# A4980.net
KiCad netlist of a schematic drawn in EAGLE
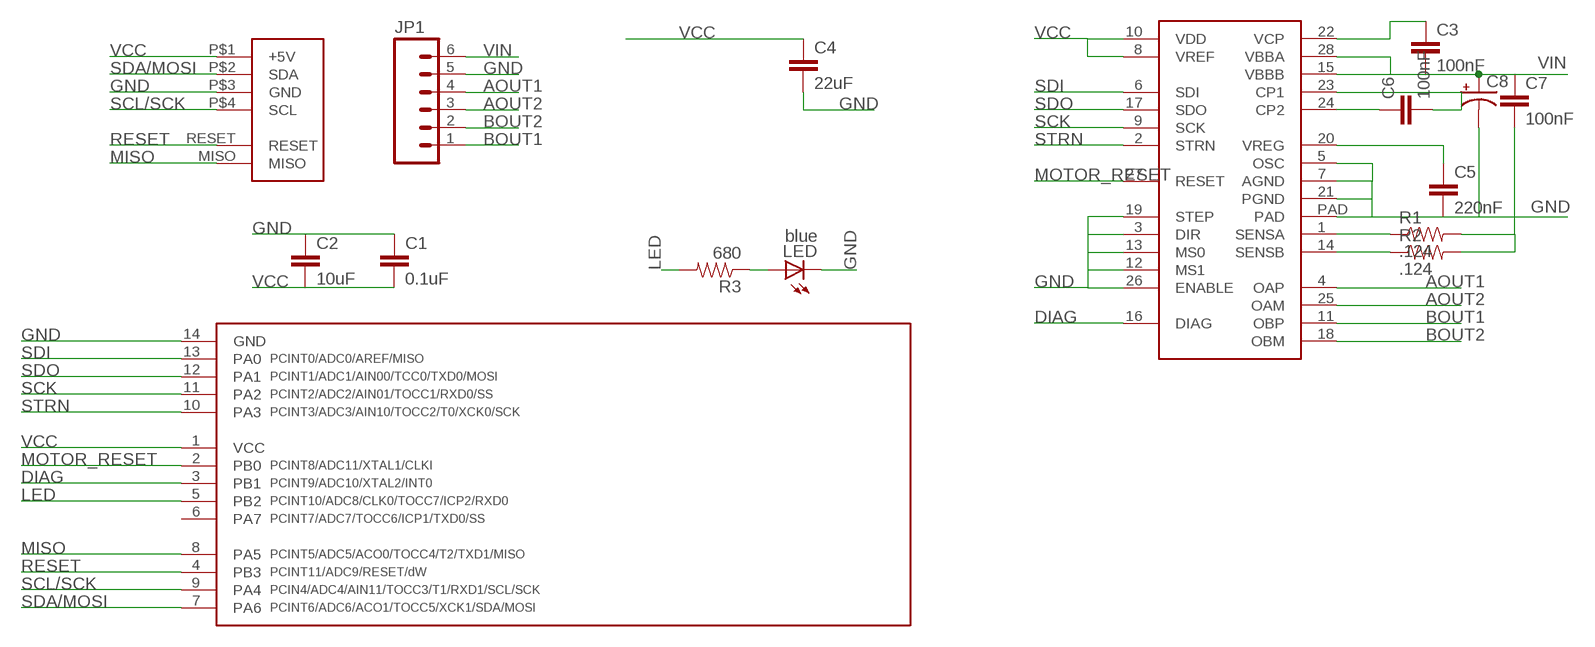
[diagram p0: schematic, sheet 1]

(export (version "E")
  (design (tool "Eeschema 10.0.6"))
  (components
    (comp (ref "C1")
      (value "0.1uF")
      (footprint "eagle-import:0805")
      (libsource (lib "eagle-import") (part "CAP0805"))
    )
    (comp (ref "C2")
      (value "10uF")
      (footprint "eagle-import:0805")
      (libsource (lib "eagle-import") (part "CAP0805"))
    )
    (comp (ref "C3")
      (value "100nF")
      (footprint "eagle-import:0805")
      (libsource (lib "eagle-import") (part "CAP0805"))
    )
    (comp (ref "C4")
      (value "22uF")
      (footprint "eagle-import:0805")
      (libsource (lib "eagle-import") (part "22UF-6.3V-20%(0805)"))
    )
    (comp (ref "C5")
      (value "220nF")
      (footprint "eagle-import:0805")
      (libsource (lib "eagle-import") (part "CAP0805"))
    )
    (comp (ref "C6")
      (value "100nF")
      (footprint "eagle-import:0805")
      (libsource (lib "eagle-import") (part "CAP0805"))
    )
    (comp (ref "C7")
      (value "100nF")
      (footprint "eagle-import:0805")
      (libsource (lib "eagle-import") (part "CAP0805"))
    )
    (comp (ref "C8")
      (value "CAP_POLD")
      (footprint "eagle-import:PANASONIC_D")
      (libsource (lib "eagle-import") (part "CAP_POLD"))
    )
    (comp (ref "JP1")
      (value "M06SIP")
      (footprint "eagle-import:1X06")
      (libsource (lib "eagle-import") (part "M06SIP"))
    )
    (comp (ref "LED")
      (value "blue")
      (footprint "eagle-import:CHIPLED_1206")
      (libsource (lib "eagle-import") (part "LEDCHIPLED_1206"))
    )
    (comp (ref "R1")
      (value ".124")
      (footprint "eagle-import:0805")
      (libsource (lib "eagle-import") (part "SparkFun-Resistors_RESISTOR0805-RES"))
    )
    (comp (ref "R2")
      (value ".124")
      (footprint "eagle-import:0805")
      (libsource (lib "eagle-import") (part "SparkFun-Resistors_RESISTOR0805-RES"))
    )
    (comp (ref "R3")
      (value "680")
      (footprint "eagle-import:0805")
      (libsource (lib "eagle-import") (part "RESISTOR0805-RES"))
    )
    (comp (ref "U$1")
      (value "A4980")
      (footprint "eagle-import:TSSOP-28")
      (libsource (lib "eagle-import") (part "A4980"))
    )
    (comp (ref "U$3")
      (value "TINY841")
      (footprint "eagle-import:SOIC14")
      (libsource (lib "eagle-import") (part "TINY841"))
    )
    (comp (ref "U$4")
      (value "FOOTPRINT")
      (footprint "eagle-import:FOOTPRINT")
      (libsource (lib "eagle-import") (part "FOOTPRINT"))
    )
  )
  (nets
    (net (code "1") (name "/AOUT1") (class "Default")
      (node (ref "JP1") (pin "4") (pinfunction "4_4") (pintype "passive"))
      (node (ref "U$1") (pin "4") (pinfunction "OAP_4") (pintype "bidirectional"))
    )
    (net (code "2") (name "/AOUT2") (class "Default")
      (node (ref "JP1") (pin "3") (pinfunction "3_3") (pintype "passive"))
      (node (ref "U$1") (pin "25") (pinfunction "OAM_25") (pintype "bidirectional"))
    )
    (net (code "3") (name "/BOUT1") (class "Default")
      (node (ref "JP1") (pin "1") (pinfunction "1_1") (pintype "passive"))
      (node (ref "U$1") (pin "11") (pinfunction "OBP_11") (pintype "bidirectional"))
    )
    (net (code "4") (name "/BOUT2") (class "Default")
      (node (ref "JP1") (pin "2") (pinfunction "2_2") (pintype "passive"))
      (node (ref "U$1") (pin "18") (pinfunction "OBM_18") (pintype "bidirectional"))
    )
    (net (code "5") (name "/DIAG") (class "Default")
      (node (ref "U$1") (pin "16") (pinfunction "DIAG_16") (pintype "bidirectional"))
      (node (ref "U$3") (pin "3") (pinfunction "PB1_3") (pintype "bidirectional"))
    )
    (net (code "6") (name "/GND") (class "Default")
      (node (ref "C1") (pin "1") (pinfunction "1_1") (pintype "passive"))
      (node (ref "C2") (pin "1") (pinfunction "1_1") (pintype "passive"))
      (node (ref "C4") (pin "2") (pinfunction "2_2") (pintype "passive"))
      (node (ref "C5") (pin "2") (pinfunction "2_2") (pintype "passive"))
      (node (ref "C7") (pin "2") (pinfunction "2_2") (pintype "passive"))
      (node (ref "C8") (pin "-") (pinfunction "-_-") (pintype "passive"))
      (node (ref "JP1") (pin "5") (pinfunction "5_5") (pintype "passive"))
      (node (ref "LED") (pin "C") (pinfunction "C_C") (pintype "passive"))
      (node (ref "R1") (pin "2") (pinfunction "2_2") (pintype "passive"))
      (node (ref "R2") (pin "2") (pinfunction "2_2") (pintype "passive"))
      (node (ref "U$1") (pin "12") (pinfunction "MS1_12") (pintype "bidirectional"))
      (node (ref "U$1") (pin "13") (pinfunction "MS0_13") (pintype "bidirectional"))
      (node (ref "U$1") (pin "19") (pinfunction "STEP_19") (pintype "bidirectional"))
      (node (ref "U$1") (pin "21") (pinfunction "PGND_21") (pintype "bidirectional"))
      (node (ref "U$1") (pin "26") (pinfunction "ENABLE_26") (pintype "bidirectional"))
      (node (ref "U$1") (pin "3") (pinfunction "DIR_3") (pintype "bidirectional"))
      (node (ref "U$1") (pin "5") (pinfunction "OSC_5") (pintype "bidirectional"))
      (node (ref "U$1") (pin "7") (pinfunction "AGND_7") (pintype "bidirectional"))
      (node (ref "U$1") (pin "PAD") (pinfunction "PAD_PAD") (pintype "bidirectional"))
      (node (ref "U$3") (pin "14") (pinfunction "GND_14") (pintype "bidirectional"))
      (node (ref "U$4") (pin "P$3") (pinfunction "GND_P$3") (pintype "power_in"))
    )
    (net (code "7") (name "/LED") (class "Default")
      (node (ref "R3") (pin "2") (pinfunction "2_2") (pintype "passive"))
      (node (ref "U$3") (pin "5") (pinfunction "PB2_5") (pintype "bidirectional"))
    )
    (net (code "8") (name "/MISO") (class "Default")
      (node (ref "U$3") (pin "8") (pinfunction "PA5_8") (pintype "bidirectional"))
      (node (ref "U$4") (pin "MISO") (pinfunction "MISO_MISO") (pintype "bidirectional"))
    )
    (net (code "9") (name "/MOTOR_RESET") (class "Default")
      (node (ref "U$1") (pin "27") (pinfunction "RESET_27") (pintype "bidirectional"))
      (node (ref "U$3") (pin "2") (pinfunction "PB0_2") (pintype "bidirectional"))
    )
    (net (code "10") (name "/RESET") (class "Default")
      (node (ref "U$3") (pin "4") (pinfunction "PB3_4") (pintype "bidirectional"))
      (node (ref "U$4") (pin "RESET") (pinfunction "RESET_RESET") (pintype "bidirectional"))
    )
    (net (code "11") (name "/SCK") (class "Default")
      (node (ref "U$1") (pin "9") (pinfunction "SCK_9") (pintype "bidirectional"))
      (node (ref "U$3") (pin "11") (pinfunction "PA2_11") (pintype "bidirectional"))
    )
    (net (code "12") (name "/SCL{slash}SCK") (class "Default")
      (node (ref "U$3") (pin "9") (pinfunction "PA4_9") (pintype "bidirectional"))
      (node (ref "U$4") (pin "P$4") (pinfunction "SCL_P$4") (pintype "bidirectional"))
    )
    (net (code "13") (name "/SDA{slash}MOSI") (class "Default")
      (node (ref "U$3") (pin "7") (pinfunction "PA6_7") (pintype "bidirectional"))
      (node (ref "U$4") (pin "P$2") (pinfunction "SDA_P$2") (pintype "bidirectional"))
    )
    (net (code "14") (name "/SDI") (class "Default")
      (node (ref "U$1") (pin "6") (pinfunction "SDI_6") (pintype "bidirectional"))
      (node (ref "U$3") (pin "13") (pinfunction "PA0_13") (pintype "bidirectional"))
    )
    (net (code "15") (name "/SDO") (class "Default")
      (node (ref "U$1") (pin "17") (pinfunction "SDO_17") (pintype "bidirectional"))
      (node (ref "U$3") (pin "12") (pinfunction "PA1_12") (pintype "bidirectional"))
    )
    (net (code "16") (name "/STRN") (class "Default")
      (node (ref "U$1") (pin "2") (pinfunction "STRN_2") (pintype "bidirectional"))
      (node (ref "U$3") (pin "10") (pinfunction "PA3_10") (pintype "bidirectional"))
    )
    (net (code "17") (name "/VCC") (class "Default")
      (node (ref "C1") (pin "2") (pinfunction "2_2") (pintype "passive"))
      (node (ref "C2") (pin "2") (pinfunction "2_2") (pintype "passive"))
      (node (ref "C4") (pin "1") (pinfunction "1_1") (pintype "passive"))
      (node (ref "U$1") (pin "10") (pinfunction "VDD_10") (pintype "bidirectional"))
      (node (ref "U$1") (pin "8") (pinfunction "VREF_8") (pintype "bidirectional"))
      (node (ref "U$3") (pin "1") (pinfunction "VCC_1") (pintype "bidirectional"))
      (node (ref "U$4") (pin "P$1") (pinfunction "+5V_P$1") (pintype "power_in"))
    )
    (net (code "18") (name "/VIN") (class "Default")
      (node (ref "C3") (pin "2") (pinfunction "2_2") (pintype "passive"))
      (node (ref "C7") (pin "1") (pinfunction "1_1") (pintype "passive"))
      (node (ref "C8") (pin "+") (pinfunction "+_+") (pintype "passive"))
      (node (ref "JP1") (pin "6") (pinfunction "6_6") (pintype "passive"))
      (node (ref "U$1") (pin "15") (pinfunction "VBBB_15") (pintype "bidirectional"))
      (node (ref "U$1") (pin "28") (pinfunction "VBBA_28") (pintype "bidirectional"))
    )
    (net (code "19") (name "Net-(LED-PadA)") (class "Default")
      (node (ref "LED") (pin "A") (pinfunction "A_A") (pintype "passive"))
      (node (ref "R3") (pin "1") (pinfunction "1_1") (pintype "passive"))
    )
    (net (code "20") (name "Net-(U$1-CP1)") (class "Default")
      (node (ref "C6") (pin "2") (pinfunction "2_2") (pintype "passive"))
      (node (ref "U$1") (pin "23") (pinfunction "CP1_23") (pintype "bidirectional"))
    )
    (net (code "21") (name "Net-(U$1-CP2)") (class "Default")
      (node (ref "C6") (pin "1") (pinfunction "1_1") (pintype "passive"))
      (node (ref "U$1") (pin "24") (pinfunction "CP2_24") (pintype "bidirectional"))
    )
    (net (code "22") (name "Net-(U$1-SENSA)") (class "Default")
      (node (ref "R1") (pin "1") (pinfunction "1_1") (pintype "passive"))
      (node (ref "U$1") (pin "1") (pinfunction "SENSA_1") (pintype "bidirectional"))
    )
    (net (code "23") (name "Net-(U$1-SENSB)") (class "Default")
      (node (ref "R2") (pin "1") (pinfunction "1_1") (pintype "passive"))
      (node (ref "U$1") (pin "14") (pinfunction "SENSB_14") (pintype "bidirectional"))
    )
    (net (code "24") (name "Net-(U$1-VCP)") (class "Default")
      (node (ref "C3") (pin "1") (pinfunction "1_1") (pintype "passive"))
      (node (ref "U$1") (pin "22") (pinfunction "VCP_22") (pintype "bidirectional"))
    )
    (net (code "25") (name "Net-(U$1-VREG)") (class "Default")
      (node (ref "C5") (pin "1") (pinfunction "1_1") (pintype "passive"))
      (node (ref "U$1") (pin "20") (pinfunction "VREG_20") (pintype "bidirectional"))
    )
    (net (code "26") (name "unconnected-(U$3-PA7-Pad6)") (class "Default")
      (node (ref "U$3") (pin "6") (pinfunction "PA7_6") (pintype "bidirectional"))
    )
  )
)
